# SCH_PowerDistributionBoardV2_2022-03-03.net
KiCad netlist of a schematic drawn in EasyEDA
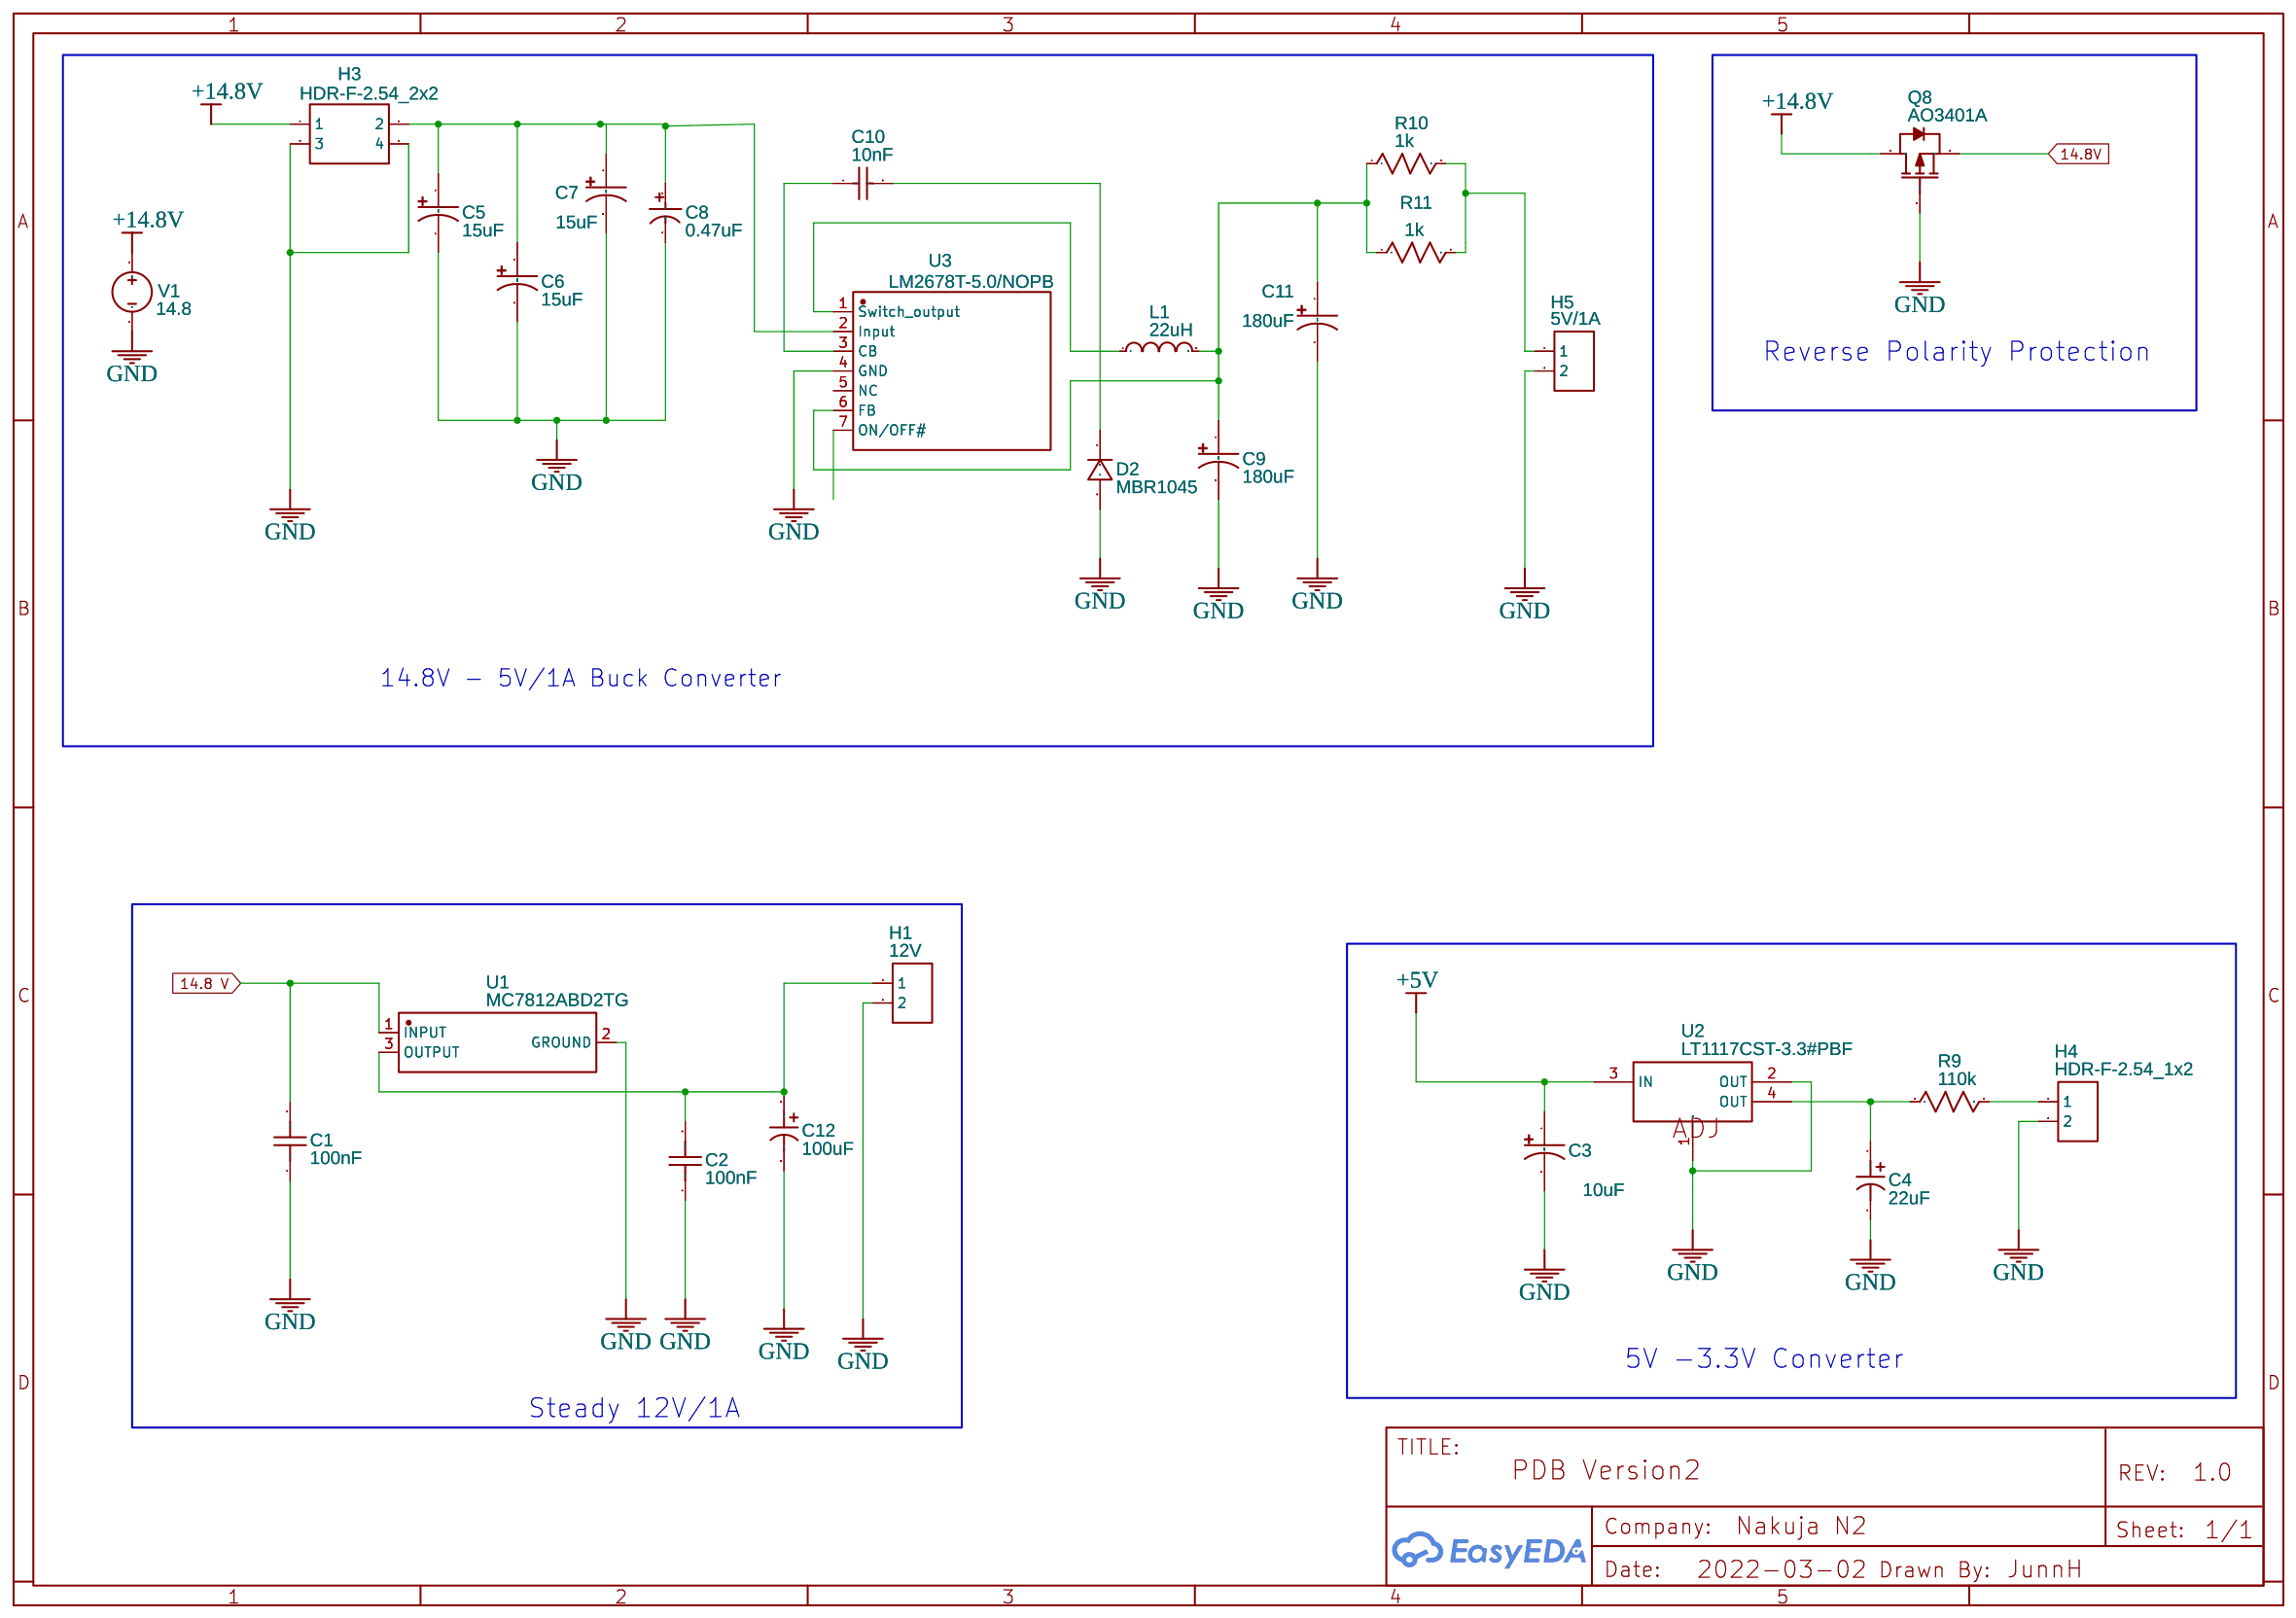
[diagram p0: schematic sheet]

(export (version "E")
  (design (tool "Eeschema 10.0.6"))
  (components
    (comp (ref "C1")
      (value "100nF")
      (fields
        (field (name "BOM_Manufacturer Part") "CC1H104ZA19D3F5P10MF")
        (field (name "BOM_Supplier Part") "C254086")
      )
      (libsource (lib "") (part "CC1H104ZA19D3F5P10MF"))
    )
    (comp (ref "C2")
      (value "100nF")
      (fields
        (field (name "BOM_Manufacturer Part") "CC1H104ZA19D3F5P10MF")
        (field (name "BOM_Supplier Part") "C254086")
      )
      (libsource (lib "") (part "CC1H104ZA19D3F5P10MF"))
    )
    (comp (ref "C3")
      (value "10uF")
      (fields
        (field (name "BOM_Manufacturer Part") "VE-100M1H0505-TRO")
        (field (name "BOM_Supplier Part") "C249452")
      )
      (libsource (lib "") (part "VE-100M1H0505-TRO"))
    )
    (comp (ref "C4")
      (value "22uF")
      (fields
        (field (name "BOM_Manufacturer Part") "RVT22UF50V67RV0028")
        (field (name "BOM_Supplier Part") "C2836438")
      )
      (libsource (lib "") (part "RVT22UF50V67RV0028"))
    )
    (comp (ref "C5")
      (value "15uF")
      (fields
        (field (name "BOM_Manufacturer Part") "UUD1H150MCL1GS")
        (field (name "BOM_Supplier Part") "C340748")
      )
      (libsource (lib "") (part "UUD1H150MCL1GS_1"))
    )
    (comp (ref "C6")
      (value "15uF")
      (fields
        (field (name "BOM_Manufacturer Part") "UUD1H150MCL1GS")
        (field (name "BOM_Supplier Part") "C340748")
      )
      (libsource (lib "") (part "UUD1H150MCL1GS_1"))
    )
    (comp (ref "C7")
      (value "15uF")
      (fields
        (field (name "BOM_Manufacturer Part") "UUD1H150MCL1GS")
        (field (name "BOM_Supplier Part") "C340748")
      )
      (libsource (lib "") (part "UUD1H150MCL1GS"))
    )
    (comp (ref "C8")
      (value "0.47uF")
      (fields
        (field (name "BOM_Manufacturer Part") "CS1HR47M-CRC54")
        (field (name "BOM_Supplier Part") "C117834")
      )
      (libsource (lib "") (part "CS1HR47M-CRC54"))
    )
    (comp (ref "C9")
      (value "180uF")
      (fields
        (field (name "BOM_Manufacturer Part") "VKMC1001C181MV")
        (field (name "BOM_Supplier Part") "C487303")
      )
      (libsource (lib "") (part "VKMC1001C181MV"))
    )
    (comp (ref "C10")
      (value "10nF")
      (fields
        (field (name "BOM_Manufacturer Part") "CL21B103KBANNNC")
        (field (name "BOM_Supplier Part") "C1710")
      )
      (libsource (lib "") (part "CL21B103KBANNNC"))
    )
    (comp (ref "C11")
      (value "180uF")
      (fields
        (field (name "BOM_Manufacturer Part") "VKMC1001C181MV")
        (field (name "BOM_Supplier Part") "C487303")
      )
      (libsource (lib "") (part "VKMC1001C181MV"))
    )
    (comp (ref "C12")
      (value "100uF")
      (fields
        (field (name "BOM_Manufacturer Part") "RVT100UF35V67RV0034")
        (field (name "BOM_Supplier Part") "C2836442")
      )
      (libsource (lib "") (part "RVT100UF35V67RV0034"))
    )
    (comp (ref "D2")
      (value "MBR1045")
      (fields (field (name "BOM_Supplier Part") "C260253"))
      (libsource (lib "") (part "MBR1045"))
    )
    (comp (ref "H1")
      (value "12V")
      (fields (field (name "BOM_Supplier Part") "C49661"))
      (libsource (lib "") (part "HDR-F-2.54_1x2"))
    )
    (comp (ref "H3")
      (value "HDR-F-2.54_2x2")
      (fields (field (name "BOM_Supplier Part") "C239342"))
      (libsource (lib "") (part "HDR-F-2.54_2x2"))
    )
    (comp (ref "H4")
      (value "HDR-F-2.54_1x2")
      (fields (field (name "BOM_Supplier Part") "C49661"))
      (libsource (lib "") (part "HDR-F-2.54_1x2"))
    )
    (comp (ref "H5")
      (value "5V/1A")
      (fields (field (name "BOM_Supplier Part") "C49661"))
      (libsource (lib "") (part "HDR-F-2.54_1x2"))
    )
    (comp (ref "L1")
      (value "22uH")
      (fields
        (field (name "BOM_Manufacturer Part") "SLO0630H220MTT")
        (field (name "BOM_Supplier Part") "C207843")
      )
      (libsource (lib "") (part "SLO0630H220MTT"))
    )
    (comp (ref "Q8")
      (value "AO3401A")
      (fields (field (name "BOM_Supplier Part") "C15127"))
      (libsource (lib "") (part "AO3401A"))
    )
    (comp (ref "R9") (value "110k") (libsource (lib "") (part "R_0603_US")))
    (comp (ref "R10") (value "1k") (libsource (lib "") (part "R_0603_US")))
    (comp (ref "R11") (value "1k") (libsource (lib "") (part "R_0603_US")))
    (comp (ref "U1")
      (value "MC7812ABD2TG")
      (fields (field (name "BOM_Supplier Part") "C154818"))
      (libsource (lib "") (part "MC7812ABD2TG"))
    )
    (comp (ref "U2")
      (value "LT1117CST-3.3#PBF")
      (fields (field (name "BOM_Supplier Part") "C140395"))
      (libsource (lib "") (part "LT1117CST-3.3#PBF"))
    )
    (comp (ref "U3")
      (value "LM2678T-5.0/NOPB")
      (fields (field (name "BOM_Supplier Part") "C390086"))
      (libsource (lib "") (part "LM2678T-5.0/NOPB"))
    )
    (comp (ref "V1") (value "14.8") (libsource (lib "") (part "VDC")))
  )
  (nets
    (net (code "1") (name "+5V") (class "Default")
      (node (ref "C3") (pin "1") (pinfunction "1_1") (pintype "unspecified"))
      (node (ref "U2") (pin "3") (pinfunction "IN_3") (pintype "passive"))
    )
    (net (code "2") (name "+14.8V") (class "Default")
      (node (ref "H3") (pin "1") (pinfunction "1_1") (pintype "unspecified"))
      (node (ref "Q8") (pin "3") (pinfunction "D_3") (pintype "unspecified"))
      (node (ref "V1") (pin "1") (pinfunction "1_1") (pintype "unspecified"))
    )
    (net (code "3") (name "14.8 V") (class "Default")
      (node (ref "C1") (pin "2") (pinfunction "2_2") (pintype "unspecified"))
      (node (ref "U1") (pin "1") (pinfunction "INPUT_1") (pintype "unspecified"))
    )
    (net (code "4") (name "14.8V") (class "Default")
      (node (ref "Q8") (pin "2") (pinfunction "S_2") (pintype "unspecified"))
    )
    (net (code "5") (name "GND") (class "Default")
      (node (ref "C1") (pin "1") (pinfunction "1_1") (pintype "unspecified"))
      (node (ref "C11") (pin "2") (pinfunction "2_2") (pintype "unspecified"))
      (node (ref "C12") (pin "2") (pinfunction "2_2") (pintype "input"))
      (node (ref "C2") (pin "1") (pinfunction "1_1") (pintype "unspecified"))
      (node (ref "C3") (pin "2") (pinfunction "2_2") (pintype "unspecified"))
      (node (ref "C4") (pin "2") (pinfunction "2_2") (pintype "input"))
      (node (ref "C5") (pin "2") (pinfunction "2_2") (pintype "unspecified"))
      (node (ref "C6") (pin "2") (pinfunction "2_2") (pintype "unspecified"))
      (node (ref "C7") (pin "2") (pinfunction "2_2") (pintype "unspecified"))
      (node (ref "C8") (pin "2") (pinfunction "2_2") (pintype "input"))
      (node (ref "C9") (pin "2") (pinfunction "2_2") (pintype "unspecified"))
      (node (ref "D2") (pin "2") (pinfunction "A_2") (pintype "unspecified"))
      (node (ref "H1") (pin "2") (pinfunction "2_2") (pintype "input"))
      (node (ref "H3") (pin "3") (pinfunction "3_3") (pintype "unspecified"))
      (node (ref "H3") (pin "4") (pinfunction "4_4") (pintype "unspecified"))
      (node (ref "H4") (pin "2") (pinfunction "2_2") (pintype "input"))
      (node (ref "H5") (pin "2") (pinfunction "2_2") (pintype "input"))
      (node (ref "Q8") (pin "1") (pinfunction "G_1") (pintype "unspecified"))
      (node (ref "U1") (pin "2") (pinfunction "GROUND_2") (pintype "unspecified"))
      (node (ref "U2") (pin "1") (pinfunction "ADJ_1") (pintype "passive"))
      (node (ref "U2") (pin "2") (pinfunction "OUT_2") (pintype "passive"))
      (node (ref "U3") (pin "4") (pinfunction "GND_4") (pintype "unspecified"))
      (node (ref "V1") (pin "2") (pinfunction "2_2") (pintype "unspecified"))
    )
    (net (code "6") (name "Net-(C4-Pad1)") (class "Default")
      (node (ref "C4") (pin "1") (pinfunction "1_1") (pintype "input"))
      (node (ref "R9") (pin "1") (pinfunction "1_1") (pintype "unspecified"))
      (node (ref "U2") (pin "4") (pinfunction "OUT_4") (pintype "passive"))
    )
    (net (code "7") (name "Net-(D2-C)") (class "Default")
      (node (ref "C10") (pin "2") (pinfunction "2_2") (pintype "input"))
      (node (ref "D2") (pin "1") (pinfunction "C_1") (pintype "unspecified"))
    )
    (net (code "8") (name "Net-(H4-Pad1)") (class "Default")
      (node (ref "H4") (pin "1") (pinfunction "1_1") (pintype "input"))
      (node (ref "R9") (pin "2") (pinfunction "2_2") (pintype "unspecified"))
    )
    (net (code "9") (name "Net-(H5-Pad1)") (class "Default")
      (node (ref "H5") (pin "1") (pinfunction "1_1") (pintype "input"))
      (node (ref "R10") (pin "2") (pinfunction "2_2") (pintype "unspecified"))
      (node (ref "R11") (pin "2") (pinfunction "2_2") (pintype "unspecified"))
    )
    (net (code "10") (name "Net-(U1-OUTPUT)") (class "Default")
      (node (ref "C12") (pin "1") (pinfunction "1_1") (pintype "input"))
      (node (ref "C2") (pin "2") (pinfunction "2_2") (pintype "unspecified"))
      (node (ref "H1") (pin "1") (pinfunction "1_1") (pintype "input"))
      (node (ref "U1") (pin "3") (pinfunction "OUTPUT_3") (pintype "unspecified"))
    )
    (net (code "11") (name "Net-(U3-CB)") (class "Default")
      (node (ref "C10") (pin "1") (pinfunction "1_1") (pintype "input"))
      (node (ref "U3") (pin "3") (pinfunction "CB_3") (pintype "unspecified"))
    )
    (net (code "12") (name "Net-(U3-FB)") (class "Default")
      (node (ref "C11") (pin "1") (pinfunction "1_1") (pintype "unspecified"))
      (node (ref "C9") (pin "1") (pinfunction "1_1") (pintype "unspecified"))
      (node (ref "L1") (pin "2") (pinfunction "2_2") (pintype "unspecified"))
      (node (ref "R10") (pin "1") (pinfunction "1_1") (pintype "unspecified"))
      (node (ref "R11") (pin "1") (pinfunction "1_1") (pintype "unspecified"))
      (node (ref "U3") (pin "6") (pinfunction "FB_6") (pintype "unspecified"))
    )
    (net (code "13") (name "Net-(U3-Input)") (class "Default")
      (node (ref "C5") (pin "1") (pinfunction "1_1") (pintype "unspecified"))
      (node (ref "C6") (pin "1") (pinfunction "1_1") (pintype "unspecified"))
      (node (ref "C7") (pin "1") (pinfunction "1_1") (pintype "unspecified"))
      (node (ref "C8") (pin "1") (pinfunction "1_1") (pintype "input"))
      (node (ref "H3") (pin "2") (pinfunction "2_2") (pintype "unspecified"))
      (node (ref "U3") (pin "2") (pinfunction "Input_2") (pintype "unspecified"))
    )
    (net (code "14") (name "Net-(U3-Switch_output)") (class "Default")
      (node (ref "L1") (pin "1") (pinfunction "1_1") (pintype "unspecified"))
      (node (ref "U3") (pin "1") (pinfunction "Switch_output_1") (pintype "unspecified"))
    )
    (net (code "15") (name "unconnected-(U3-NC-Pad5)") (class "Default")
      (node (ref "U3") (pin "5") (pinfunction "NC_5") (pintype "unspecified"))
    )
    (net (code "16") (name "unconnected-(U3-ON{slash}OFF#-Pad7)") (class "Default")
      (node (ref "U3") (pin "7") (pinfunction "ON/OFF#_7") (pintype "unspecified"))
    )
  )
)
